# xenium-programmer-rpi.net
KiCad netlist of a schematic drawn in EAGLE
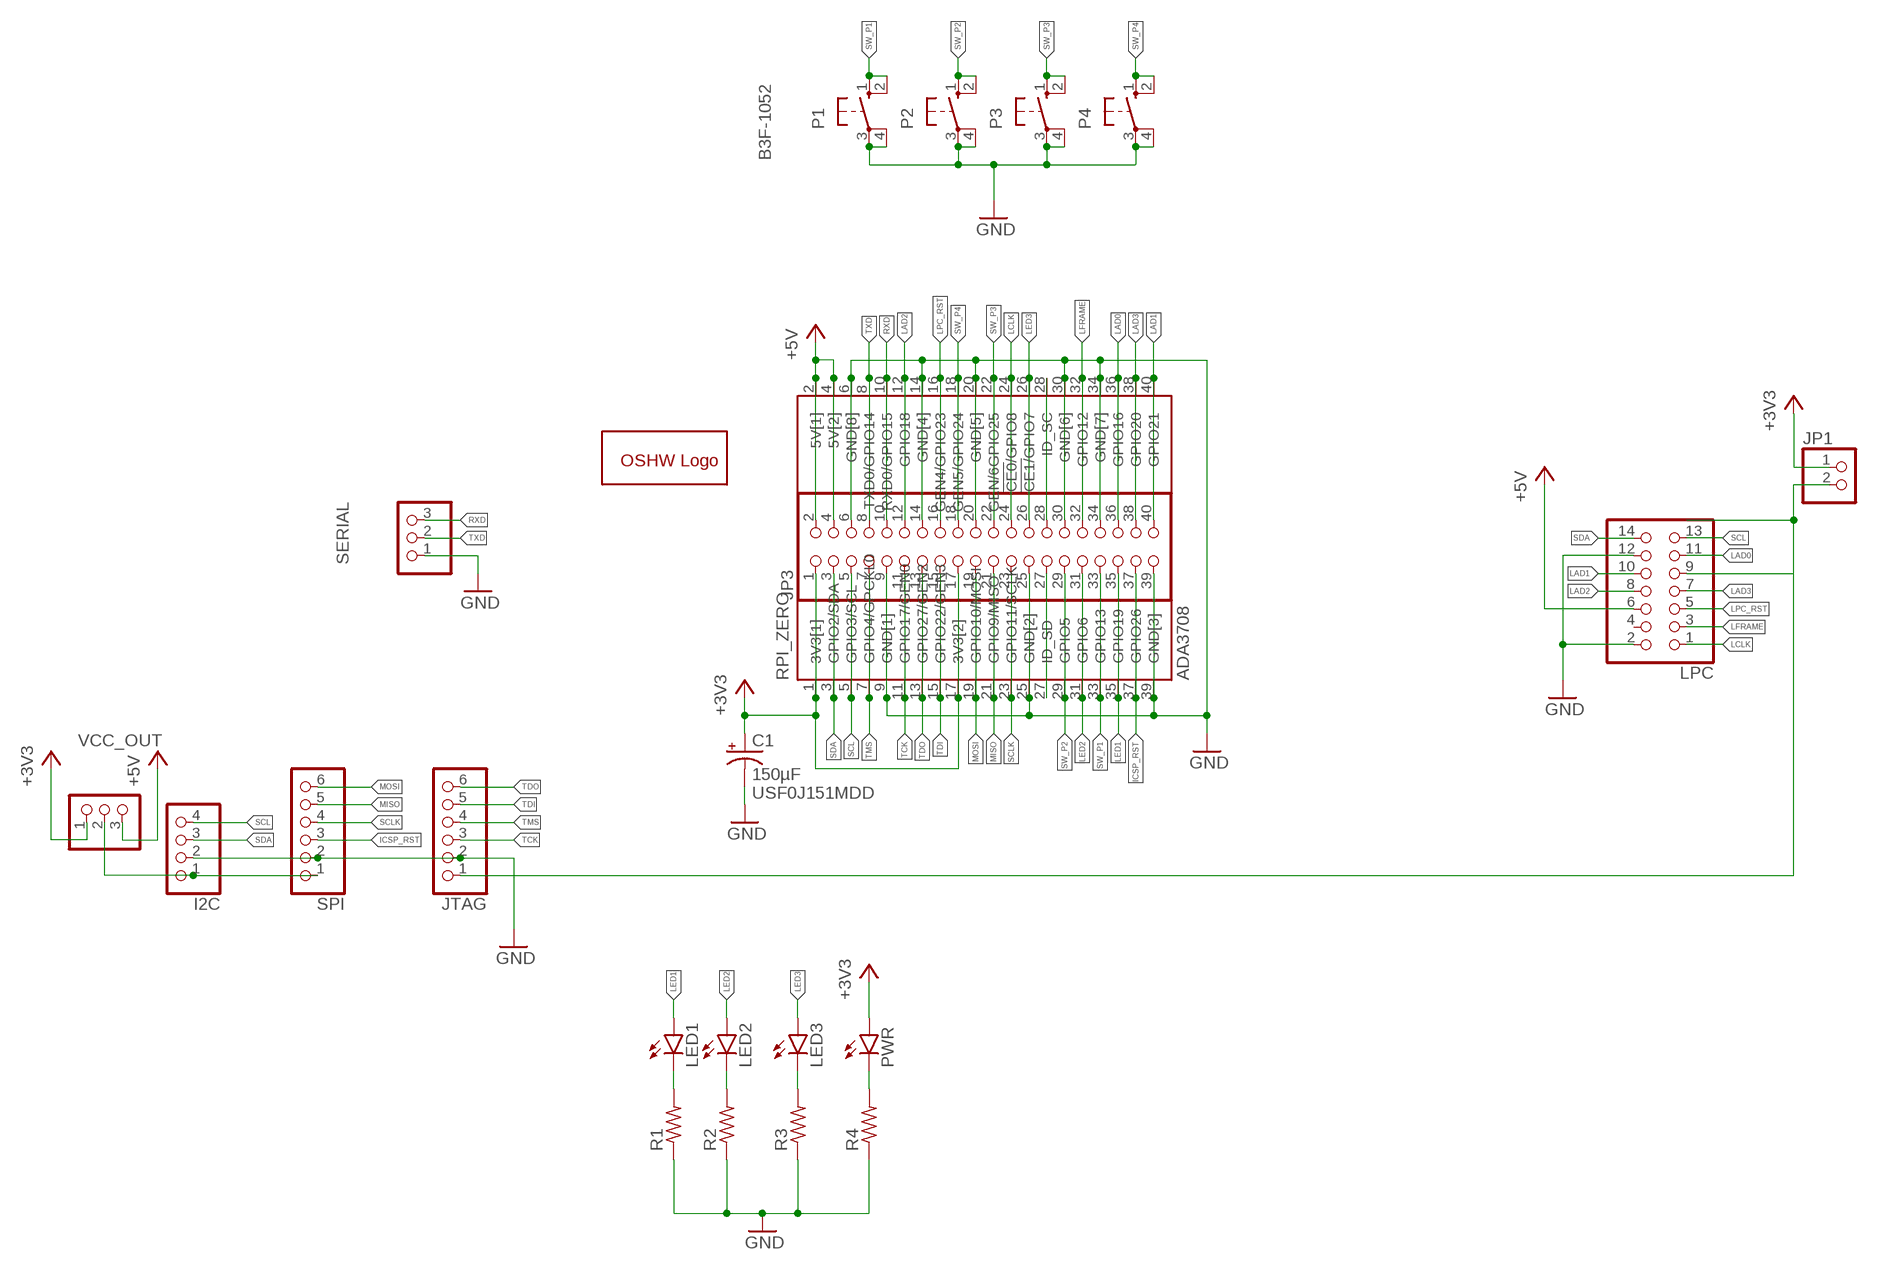
[diagram p0: schematic, sheet 1]

(export (version "E")
  (design (tool "Eeschema 10.0.6"))
  (components
    (comp (ref "C1")
      (value "150µF")
      (footprint "eagle-import:E3,5-8")
      (libsource (lib "eagle-import") (part "CPOL-USE3.5-8"))
    )
    (comp (ref "GOLD_ORB_SM1")
      (value "OSHWLOGOLOGO8MM")
      (footprint "eagle-import:OSHW_8MM")
      (libsource (lib "eagle-import") (part "OSHWLOGOLOGO8MM"))
    )
    (comp (ref "I2C")
      (value "PINHD-1X4")
      (footprint "eagle-import:1X04")
      (libsource (lib "eagle-import") (part "PINHD-1X4"))
    )
    (comp (ref "JP1")
      (value "PINHD-1X2")
      (footprint "eagle-import:1X02")
      (libsource (lib "eagle-import") (part "PINHD-1X2"))
    )
    (comp (ref "JP3")
      (value "PINHD-2X20")
      (footprint "eagle-import:2X20")
      (libsource (lib "eagle-import") (part "PINHD-2X20"))
    )
    (comp (ref "JTAG")
      (value "PINHD-1X6")
      (footprint "eagle-import:1X06")
      (libsource (lib "eagle-import") (part "PINHD-1X6"))
    )
    (comp (ref "LED1")
      (value "LED5MM")
      (footprint "eagle-import:LED5MM")
      (libsource (lib "eagle-import") (part "LED5MM"))
    )
    (comp (ref "LED2")
      (value "LED5MM")
      (footprint "eagle-import:LED5MM")
      (libsource (lib "eagle-import") (part "LED5MM"))
    )
    (comp (ref "LED3")
      (value "LED5MM")
      (footprint "eagle-import:LED5MM")
      (libsource (lib "eagle-import") (part "LED5MM"))
    )
    (comp (ref "LPC")
      (value "PINHD-2X7")
      (footprint "eagle-import:2X07")
      (libsource (lib "eagle-import") (part "PINHD-2X7"))
    )
    (comp (ref "P1")
      (value "B3F-1052")
      (footprint "eagle-import:B3F-10XX")
      (fields (field (name "MF") "Omron"))
      (libsource (lib "eagle-import") (part "B3F-1052"))
    )
    (comp (ref "P2")
      (value "B3F-1052")
      (footprint "eagle-import:B3F-10XX")
      (fields (field (name "MF") "Omron"))
      (libsource (lib "eagle-import") (part "B3F-1052"))
    )
    (comp (ref "P3")
      (value "B3F-1052")
      (footprint "eagle-import:B3F-10XX")
      (fields (field (name "MF") "Omron"))
      (libsource (lib "eagle-import") (part "B3F-1052"))
    )
    (comp (ref "P4")
      (value "B3F-1052")
      (footprint "eagle-import:B3F-10XX")
      (fields (field (name "MF") "Omron"))
      (libsource (lib "eagle-import") (part "B3F-1052"))
    )
    (comp (ref "PWR")
      (value "LED5MM")
      (footprint "eagle-import:LED5MM")
      (libsource (lib "eagle-import") (part "LED5MM"))
    )
    (comp (ref "R1")
      (value "R-US_0207/10")
      (footprint "eagle-import:0207_10")
      (libsource (lib "eagle-import") (part "R-US_0207/10"))
    )
    (comp (ref "R2")
      (value "R-US_0207/10")
      (footprint "eagle-import:0207_10")
      (libsource (lib "eagle-import") (part "R-US_0207/10"))
    )
    (comp (ref "R3")
      (value "R-US_0207/10")
      (footprint "eagle-import:0207_10")
      (libsource (lib "eagle-import") (part "R-US_0207/10"))
    )
    (comp (ref "R4")
      (value "R-US_0207/10")
      (footprint "eagle-import:0207_10")
      (libsource (lib "eagle-import") (part "R-US_0207/10"))
    )
    (comp (ref "RPI_ZERO")
      (value "ADA3708")
      (footprint "eagle-import:ADA3708_RPI-ZERO")
      (fields (field (name "MF") "Raspberry Pi"))
      (libsource (lib "eagle-import") (part "ADA3708"))
    )
    (comp (ref "SERIAL")
      (value "PINHD-1X3")
      (footprint "eagle-import:1X03")
      (libsource (lib "eagle-import") (part "PINHD-1X3"))
    )
    (comp (ref "SPI")
      (value "PINHD-1X6")
      (footprint "eagle-import:1X06")
      (libsource (lib "eagle-import") (part "PINHD-1X6"))
    )
    (comp (ref "VCC_OUT")
      (value "PINHD-1X3")
      (footprint "eagle-import:1X03")
      (libsource (lib "eagle-import") (part "PINHD-1X3"))
    )
  )
  (nets
    (net (code "1") (name "+3V3") (class "Default")
      (node (ref "C1") (pin "+") (pinfunction "+_+") (pintype "passive"))
      (node (ref "JP1") (pin "1") (pinfunction "1_1") (pintype "passive"))
      (node (ref "JP3") (pin "1") (pinfunction "1_1") (pintype "passive"))
      (node (ref "JP3") (pin "17") (pinfunction "17_17") (pintype "passive"))
      (node (ref "PWR") (pin "A") (pinfunction "A_A") (pintype "passive"))
      (node (ref "RPI_ZERO") (pin "1") (pinfunction "3V3[1]_1") (pintype "power_in"))
      (node (ref "RPI_ZERO") (pin "17") (pinfunction "3V3[2]_17") (pintype "power_in"))
      (node (ref "VCC_OUT") (pin "1") (pinfunction "1_1") (pintype "passive"))
    )
    (net (code "2") (name "+5V") (class "Default")
      (node (ref "JP3") (pin "2") (pinfunction "2_2") (pintype "passive"))
      (node (ref "JP3") (pin "4") (pinfunction "4_4") (pintype "passive"))
      (node (ref "LPC") (pin "6") (pinfunction "6_6") (pintype "passive"))
      (node (ref "RPI_ZERO") (pin "2") (pinfunction "5V[1]_2") (pintype "power_in"))
      (node (ref "RPI_ZERO") (pin "4") (pinfunction "5V[2]_4") (pintype "power_in"))
      (node (ref "VCC_OUT") (pin "3") (pinfunction "3_3") (pintype "passive"))
    )
    (net (code "3") (name "GND") (class "Default")
      (node (ref "C1") (pin "-") (pinfunction "-_-") (pintype "passive"))
      (node (ref "I2C") (pin "2") (pinfunction "2_2") (pintype "passive"))
      (node (ref "JP3") (pin "14") (pinfunction "14_14") (pintype "passive"))
      (node (ref "JP3") (pin "20") (pinfunction "20_20") (pintype "passive"))
      (node (ref "JP3") (pin "25") (pinfunction "25_25") (pintype "passive"))
      (node (ref "JP3") (pin "30") (pinfunction "30_30") (pintype "passive"))
      (node (ref "JP3") (pin "34") (pinfunction "34_34") (pintype "passive"))
      (node (ref "JP3") (pin "39") (pinfunction "39_39") (pintype "passive"))
      (node (ref "JP3") (pin "6") (pinfunction "6_6") (pintype "passive"))
      (node (ref "JP3") (pin "9") (pinfunction "9_9") (pintype "passive"))
      (node (ref "JTAG") (pin "2") (pinfunction "2_2") (pintype "passive"))
      (node (ref "LPC") (pin "12") (pinfunction "12_12") (pintype "passive"))
      (node (ref "LPC") (pin "2") (pinfunction "2_2") (pintype "passive"))
      (node (ref "P1") (pin "3") (pinfunction "P_3") (pintype "passive"))
      (node (ref "P1") (pin "4") (pinfunction "P1_4") (pintype "passive"))
      (node (ref "P2") (pin "3") (pinfunction "P_3") (pintype "passive"))
      (node (ref "P2") (pin "4") (pinfunction "P1_4") (pintype "passive"))
      (node (ref "P3") (pin "3") (pinfunction "P_3") (pintype "passive"))
      (node (ref "P3") (pin "4") (pinfunction "P1_4") (pintype "passive"))
      (node (ref "P4") (pin "3") (pinfunction "P_3") (pintype "passive"))
      (node (ref "P4") (pin "4") (pinfunction "P1_4") (pintype "passive"))
      (node (ref "R1") (pin "1") (pinfunction "1_1") (pintype "passive"))
      (node (ref "R2") (pin "1") (pinfunction "1_1") (pintype "passive"))
      (node (ref "R3") (pin "1") (pinfunction "1_1") (pintype "passive"))
      (node (ref "R4") (pin "1") (pinfunction "1_1") (pintype "passive"))
      (node (ref "RPI_ZERO") (pin "14") (pinfunction "GND[4]_14") (pintype "power_in"))
      (node (ref "RPI_ZERO") (pin "20") (pinfunction "GND[5]_20") (pintype "power_in"))
      (node (ref "RPI_ZERO") (pin "25") (pinfunction "GND[2]_25") (pintype "power_in"))
      (node (ref "RPI_ZERO") (pin "30") (pinfunction "GND[6]_30") (pintype "power_in"))
      (node (ref "RPI_ZERO") (pin "34") (pinfunction "GND[7]_34") (pintype "power_in"))
      (node (ref "RPI_ZERO") (pin "39") (pinfunction "GND[3]_39") (pintype "power_in"))
      (node (ref "RPI_ZERO") (pin "6") (pinfunction "GND[8]_6") (pintype "power_in"))
      (node (ref "RPI_ZERO") (pin "9") (pinfunction "GND[1]_9") (pintype "power_in"))
      (node (ref "SERIAL") (pin "1") (pinfunction "1_1") (pintype "passive"))
      (node (ref "SPI") (pin "2") (pinfunction "2_2") (pintype "passive"))
    )
    (net (code "4") (name "ICSP_RST") (class "Default")
      (node (ref "JP3") (pin "37") (pinfunction "37_37") (pintype "passive"))
      (node (ref "RPI_ZERO") (pin "37") (pinfunction "GPIO26_37") (pintype "bidirectional"))
      (node (ref "SPI") (pin "3") (pinfunction "3_3") (pintype "passive"))
    )
    (net (code "5") (name "LAD0") (class "Default")
      (node (ref "JP3") (pin "36") (pinfunction "36_36") (pintype "passive"))
      (node (ref "LPC") (pin "11") (pinfunction "11_11") (pintype "passive"))
      (node (ref "RPI_ZERO") (pin "36") (pinfunction "GPIO16_36") (pintype "bidirectional"))
    )
    (net (code "6") (name "LAD1") (class "Default")
      (node (ref "JP3") (pin "40") (pinfunction "40_40") (pintype "passive"))
      (node (ref "LPC") (pin "10") (pinfunction "10_10") (pintype "passive"))
      (node (ref "RPI_ZERO") (pin "40") (pinfunction "GPIO21_40") (pintype "bidirectional"))
    )
    (net (code "7") (name "LAD2") (class "Default")
      (node (ref "JP3") (pin "12") (pinfunction "12_12") (pintype "passive"))
      (node (ref "LPC") (pin "8") (pinfunction "8_8") (pintype "passive"))
      (node (ref "RPI_ZERO") (pin "12") (pinfunction "GPIO18_12") (pintype "bidirectional"))
    )
    (net (code "8") (name "LAD3") (class "Default")
      (node (ref "JP3") (pin "38") (pinfunction "38_38") (pintype "passive"))
      (node (ref "LPC") (pin "7") (pinfunction "7_7") (pintype "passive"))
      (node (ref "RPI_ZERO") (pin "38") (pinfunction "GPIO20_38") (pintype "bidirectional"))
    )
    (net (code "9") (name "LCLK") (class "Default")
      (node (ref "JP3") (pin "24") (pinfunction "24_24") (pintype "passive"))
      (node (ref "LPC") (pin "1") (pinfunction "1_1") (pintype "passive"))
      (node (ref "RPI_ZERO") (pin "24") (pinfunction "~{CE0}/GPIO8_24") (pintype "bidirectional"))
    )
    (net (code "10") (name "LED1") (class "Default")
      (node (ref "JP3") (pin "35") (pinfunction "35_35") (pintype "passive"))
      (node (ref "LED1") (pin "A") (pinfunction "A_A") (pintype "passive"))
      (node (ref "RPI_ZERO") (pin "35") (pinfunction "GPIO19_35") (pintype "bidirectional"))
    )
    (net (code "11") (name "LED2") (class "Default")
      (node (ref "JP3") (pin "31") (pinfunction "31_31") (pintype "passive"))
      (node (ref "LED2") (pin "A") (pinfunction "A_A") (pintype "passive"))
      (node (ref "RPI_ZERO") (pin "31") (pinfunction "GPIO6_31") (pintype "bidirectional"))
    )
    (net (code "12") (name "LED3") (class "Default")
      (node (ref "JP3") (pin "26") (pinfunction "26_26") (pintype "passive"))
      (node (ref "LED3") (pin "A") (pinfunction "A_A") (pintype "passive"))
      (node (ref "RPI_ZERO") (pin "26") (pinfunction "~{CE1/}GPIO7_26") (pintype "bidirectional"))
    )
    (net (code "13") (name "LFRAME") (class "Default")
      (node (ref "JP3") (pin "32") (pinfunction "32_32") (pintype "passive"))
      (node (ref "LPC") (pin "3") (pinfunction "3_3") (pintype "passive"))
      (node (ref "RPI_ZERO") (pin "32") (pinfunction "GPIO12_32") (pintype "bidirectional"))
    )
    (net (code "14") (name "LPC_RST") (class "Default")
      (node (ref "JP3") (pin "16") (pinfunction "16_16") (pintype "passive"))
      (node (ref "LPC") (pin "5") (pinfunction "5_5") (pintype "passive"))
      (node (ref "RPI_ZERO") (pin "16") (pinfunction "GEN4/GPIO23_16") (pintype "bidirectional"))
    )
    (net (code "15") (name "MISO") (class "Default")
      (node (ref "JP3") (pin "21") (pinfunction "21_21") (pintype "passive"))
      (node (ref "RPI_ZERO") (pin "21") (pinfunction "GPIO9/MISO_21") (pintype "bidirectional"))
      (node (ref "SPI") (pin "5") (pinfunction "5_5") (pintype "passive"))
    )
    (net (code "16") (name "MOSI") (class "Default")
      (node (ref "JP3") (pin "19") (pinfunction "19_19") (pintype "passive"))
      (node (ref "RPI_ZERO") (pin "19") (pinfunction "GPIO10/MOSI_19") (pintype "bidirectional"))
      (node (ref "SPI") (pin "6") (pinfunction "6_6") (pintype "passive"))
    )
    (net (code "17") (name "Net-(I2C-Pad1)") (class "Default")
      (node (ref "I2C") (pin "1") (pinfunction "1_1") (pintype "passive"))
      (node (ref "SPI") (pin "1") (pinfunction "1_1") (pintype "passive"))
      (node (ref "VCC_OUT") (pin "2") (pinfunction "2_2") (pintype "passive"))
    )
    (net (code "18") (name "Net-(JP1-Pad2)") (class "Default")
      (node (ref "JP1") (pin "2") (pinfunction "2_2") (pintype "passive"))
      (node (ref "JTAG") (pin "1") (pinfunction "1_1") (pintype "passive"))
      (node (ref "LPC") (pin "9") (pinfunction "9_9") (pintype "passive"))
    )
    (net (code "19") (name "Net-(LED1-C)") (class "Default")
      (node (ref "LED1") (pin "K") (pinfunction "C_K") (pintype "passive"))
      (node (ref "R1") (pin "2") (pinfunction "2_2") (pintype "passive"))
    )
    (net (code "20") (name "Net-(LED2-C)") (class "Default")
      (node (ref "LED2") (pin "K") (pinfunction "C_K") (pintype "passive"))
      (node (ref "R2") (pin "2") (pinfunction "2_2") (pintype "passive"))
    )
    (net (code "21") (name "Net-(LED3-C)") (class "Default")
      (node (ref "LED3") (pin "K") (pinfunction "C_K") (pintype "passive"))
      (node (ref "R3") (pin "2") (pinfunction "2_2") (pintype "passive"))
    )
    (net (code "22") (name "Net-(PWR-C)") (class "Default")
      (node (ref "PWR") (pin "K") (pinfunction "C_K") (pintype "passive"))
      (node (ref "R4") (pin "2") (pinfunction "2_2") (pintype "passive"))
    )
    (net (code "23") (name "Net-(RPI_ZERO-ID_SC)") (class "Default")
      (node (ref "JP3") (pin "28") (pinfunction "28_28") (pintype "passive"))
      (node (ref "RPI_ZERO") (pin "28") (pinfunction "ID_SC_28") (pintype "bidirectional"))
    )
    (net (code "24") (name "Net-(RPI_ZERO-ID_SD)") (class "Default")
      (node (ref "JP3") (pin "27") (pinfunction "27_27") (pintype "passive"))
      (node (ref "RPI_ZERO") (pin "27") (pinfunction "ID_SD_27") (pintype "bidirectional"))
    )
    (net (code "25") (name "RXD") (class "Default")
      (node (ref "JP3") (pin "10") (pinfunction "10_10") (pintype "passive"))
      (node (ref "RPI_ZERO") (pin "10") (pinfunction "RXD0/GPIO15_10") (pintype "bidirectional"))
      (node (ref "SERIAL") (pin "3") (pinfunction "3_3") (pintype "passive"))
    )
    (net (code "26") (name "SCL") (class "Default")
      (node (ref "I2C") (pin "4") (pinfunction "4_4") (pintype "passive"))
      (node (ref "JP3") (pin "5") (pinfunction "5_5") (pintype "passive"))
      (node (ref "LPC") (pin "13") (pinfunction "13_13") (pintype "passive"))
      (node (ref "RPI_ZERO") (pin "5") (pinfunction "GPIO3/SCL_5") (pintype "bidirectional"))
    )
    (net (code "27") (name "SCLK") (class "Default")
      (node (ref "JP3") (pin "23") (pinfunction "23_23") (pintype "passive"))
      (node (ref "RPI_ZERO") (pin "23") (pinfunction "GPIO11/SCLK_23") (pintype "bidirectional"))
      (node (ref "SPI") (pin "4") (pinfunction "4_4") (pintype "passive"))
    )
    (net (code "28") (name "SDA") (class "Default")
      (node (ref "I2C") (pin "3") (pinfunction "3_3") (pintype "passive"))
      (node (ref "JP3") (pin "3") (pinfunction "3_3") (pintype "passive"))
      (node (ref "LPC") (pin "14") (pinfunction "14_14") (pintype "passive"))
      (node (ref "RPI_ZERO") (pin "3") (pinfunction "GPIO2/SDA_3") (pintype "bidirectional"))
    )
    (net (code "29") (name "SW_P1") (class "Default")
      (node (ref "JP3") (pin "33") (pinfunction "33_33") (pintype "passive"))
      (node (ref "P1") (pin "1") (pinfunction "S_1") (pintype "passive"))
      (node (ref "P1") (pin "2") (pinfunction "S1_2") (pintype "passive"))
      (node (ref "RPI_ZERO") (pin "33") (pinfunction "GPIO13_33") (pintype "bidirectional"))
    )
    (net (code "30") (name "SW_P2") (class "Default")
      (node (ref "JP3") (pin "29") (pinfunction "29_29") (pintype "passive"))
      (node (ref "P2") (pin "1") (pinfunction "S_1") (pintype "passive"))
      (node (ref "P2") (pin "2") (pinfunction "S1_2") (pintype "passive"))
      (node (ref "RPI_ZERO") (pin "29") (pinfunction "GPIO5_29") (pintype "bidirectional"))
    )
    (net (code "31") (name "SW_P3") (class "Default")
      (node (ref "JP3") (pin "22") (pinfunction "22_22") (pintype "passive"))
      (node (ref "P3") (pin "1") (pinfunction "S_1") (pintype "passive"))
      (node (ref "P3") (pin "2") (pinfunction "S1_2") (pintype "passive"))
      (node (ref "RPI_ZERO") (pin "22") (pinfunction "GEN/6GPIO25_22") (pintype "bidirectional"))
    )
    (net (code "32") (name "SW_P4") (class "Default")
      (node (ref "JP3") (pin "18") (pinfunction "18_18") (pintype "passive"))
      (node (ref "P4") (pin "1") (pinfunction "S_1") (pintype "passive"))
      (node (ref "P4") (pin "2") (pinfunction "S1_2") (pintype "passive"))
      (node (ref "RPI_ZERO") (pin "18") (pinfunction "GEN5/GPIO24_18") (pintype "bidirectional"))
    )
    (net (code "33") (name "TCK") (class "Default")
      (node (ref "JP3") (pin "11") (pinfunction "11_11") (pintype "passive"))
      (node (ref "JTAG") (pin "3") (pinfunction "3_3") (pintype "passive"))
      (node (ref "RPI_ZERO") (pin "11") (pinfunction "GPIO17/GEN0_11") (pintype "bidirectional"))
    )
    (net (code "34") (name "TDI") (class "Default")
      (node (ref "JP3") (pin "15") (pinfunction "15_15") (pintype "passive"))
      (node (ref "JTAG") (pin "5") (pinfunction "5_5") (pintype "passive"))
      (node (ref "RPI_ZERO") (pin "15") (pinfunction "GPIO22/GEN3_15") (pintype "bidirectional"))
    )
    (net (code "35") (name "TDO") (class "Default")
      (node (ref "JP3") (pin "13") (pinfunction "13_13") (pintype "passive"))
      (node (ref "JTAG") (pin "6") (pinfunction "6_6") (pintype "passive"))
      (node (ref "RPI_ZERO") (pin "13") (pinfunction "GPIO27/GEN2_13") (pintype "bidirectional"))
    )
    (net (code "36") (name "TMS") (class "Default")
      (node (ref "JP3") (pin "7") (pinfunction "7_7") (pintype "passive"))
      (node (ref "JTAG") (pin "4") (pinfunction "4_4") (pintype "passive"))
      (node (ref "RPI_ZERO") (pin "7") (pinfunction "GPIO4/GPCKL0_7") (pintype "bidirectional"))
    )
    (net (code "37") (name "TXD") (class "Default")
      (node (ref "JP3") (pin "8") (pinfunction "8_8") (pintype "passive"))
      (node (ref "RPI_ZERO") (pin "8") (pinfunction "TXD0/GPIO14_8") (pintype "bidirectional"))
      (node (ref "SERIAL") (pin "2") (pinfunction "2_2") (pintype "passive"))
    )
    (net (code "38") (name "unconnected-(LPC-Pad4)") (class "Default")
      (node (ref "LPC") (pin "4") (pinfunction "4_4") (pintype "passive"))
    )
  )
)
